# uMatrixPCB_r1_0.net
KiCad netlist of a schematic drawn in EAGLE
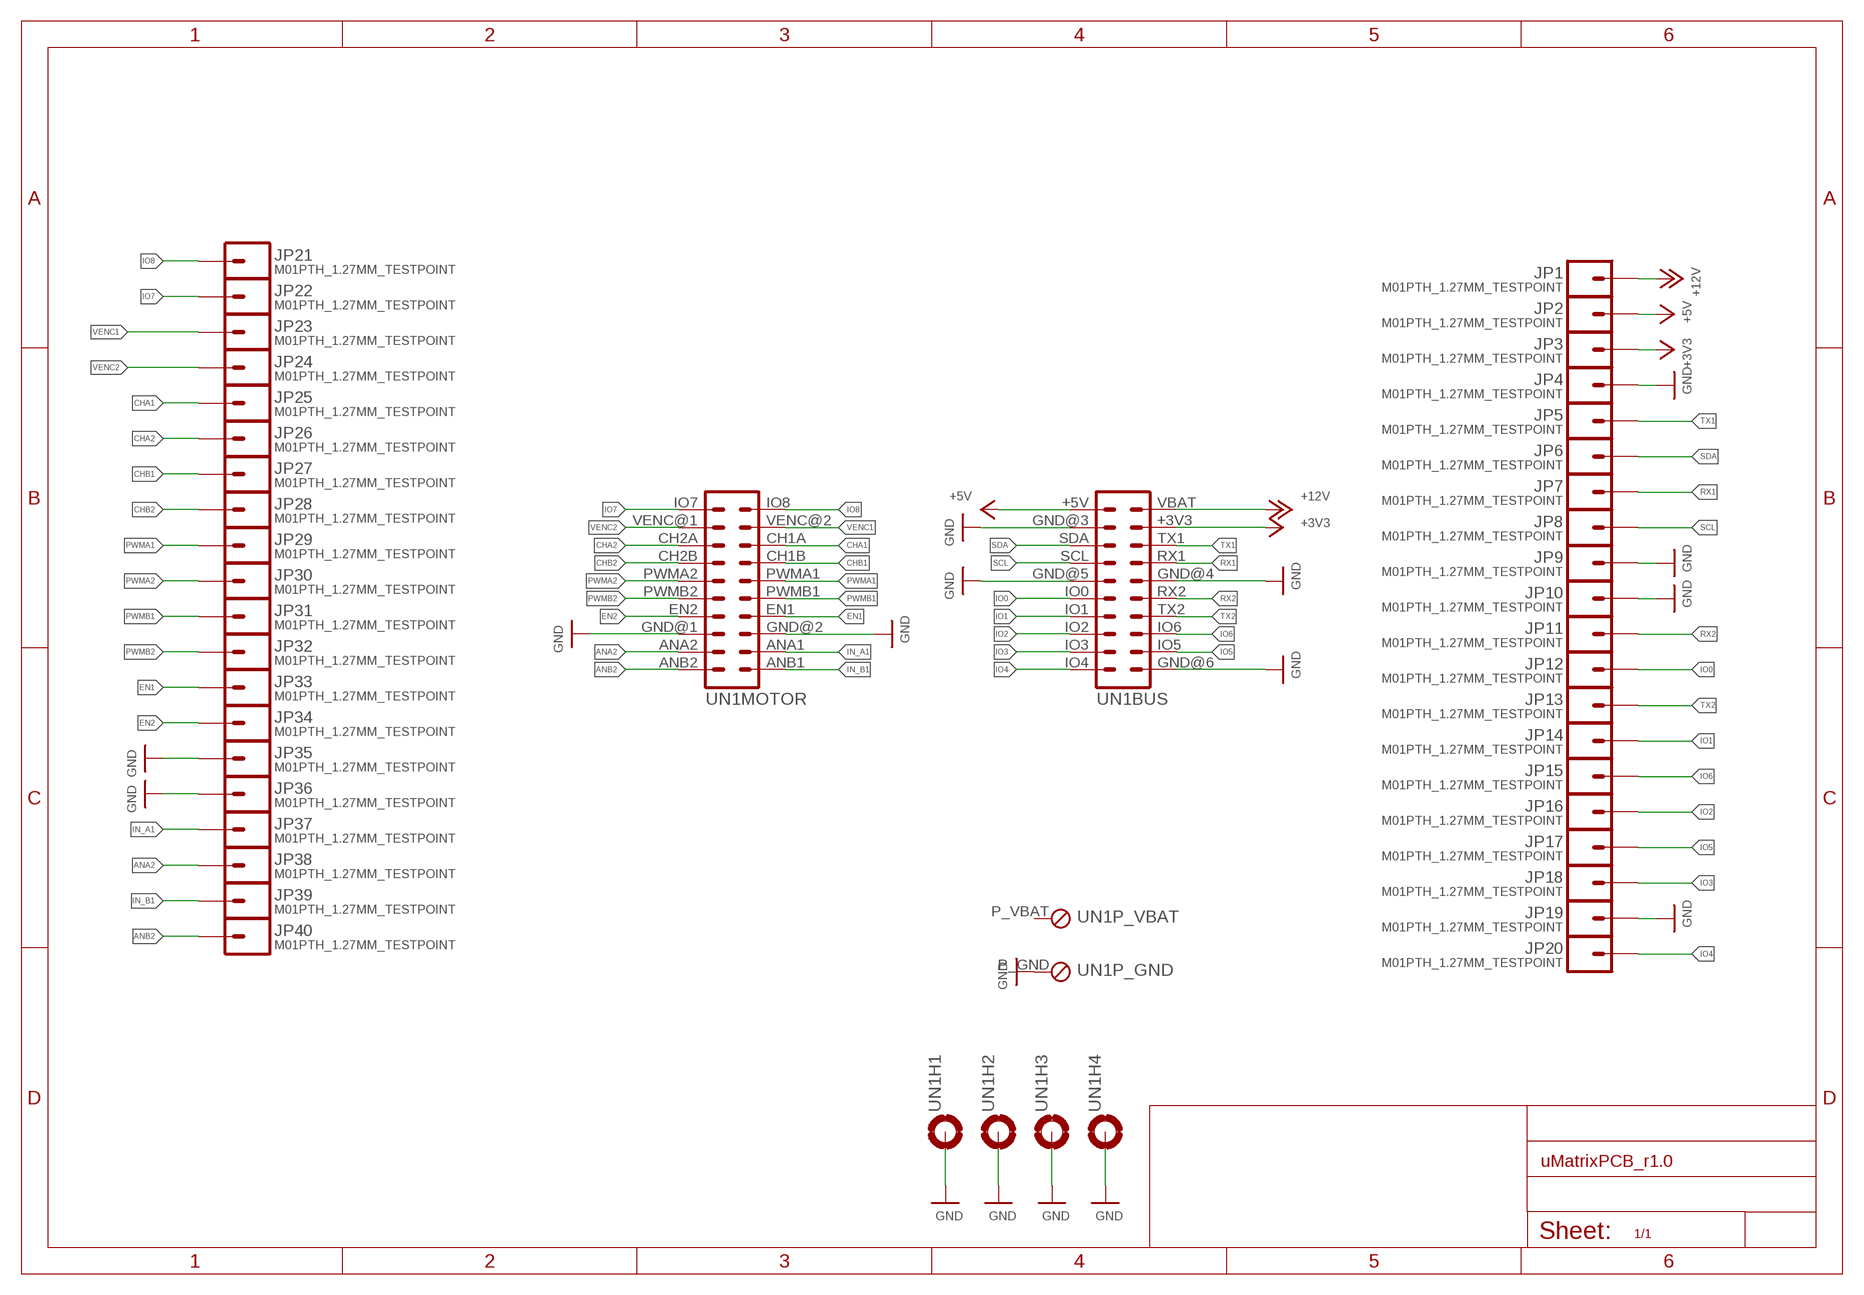
[diagram p0: schematic, sheet 1]

(export (version "E")
  (design (tool "Eeschema 10.0.6"))
  (components
    (comp (ref "JP1")
      (value "M01PTH_1.27MM_TESTPOINT")
      (footprint "eagle-import:1X0.127_TESTPOINT")
      (libsource (lib "eagle-import") (part "M01PTH_1.27MM_TESTPOINT"))
    )
    (comp (ref "JP2")
      (value "M01PTH_1.27MM_TESTPOINT")
      (footprint "eagle-import:1X0.127_TESTPOINT")
      (libsource (lib "eagle-import") (part "M01PTH_1.27MM_TESTPOINT"))
    )
    (comp (ref "JP3")
      (value "M01PTH_1.27MM_TESTPOINT")
      (footprint "eagle-import:1X0.127_TESTPOINT")
      (libsource (lib "eagle-import") (part "M01PTH_1.27MM_TESTPOINT"))
    )
    (comp (ref "JP4")
      (value "M01PTH_1.27MM_TESTPOINT")
      (footprint "eagle-import:1X0.127_TESTPOINT")
      (libsource (lib "eagle-import") (part "M01PTH_1.27MM_TESTPOINT"))
    )
    (comp (ref "JP5")
      (value "M01PTH_1.27MM_TESTPOINT")
      (footprint "eagle-import:1X0.127_TESTPOINT")
      (libsource (lib "eagle-import") (part "M01PTH_1.27MM_TESTPOINT"))
    )
    (comp (ref "JP6")
      (value "M01PTH_1.27MM_TESTPOINT")
      (footprint "eagle-import:1X0.127_TESTPOINT")
      (libsource (lib "eagle-import") (part "M01PTH_1.27MM_TESTPOINT"))
    )
    (comp (ref "JP7")
      (value "M01PTH_1.27MM_TESTPOINT")
      (footprint "eagle-import:1X0.127_TESTPOINT")
      (libsource (lib "eagle-import") (part "M01PTH_1.27MM_TESTPOINT"))
    )
    (comp (ref "JP8")
      (value "M01PTH_1.27MM_TESTPOINT")
      (footprint "eagle-import:1X0.127_TESTPOINT")
      (libsource (lib "eagle-import") (part "M01PTH_1.27MM_TESTPOINT"))
    )
    (comp (ref "JP9")
      (value "M01PTH_1.27MM_TESTPOINT")
      (footprint "eagle-import:1X0.127_TESTPOINT")
      (libsource (lib "eagle-import") (part "M01PTH_1.27MM_TESTPOINT"))
    )
    (comp (ref "JP10")
      (value "M01PTH_1.27MM_TESTPOINT")
      (footprint "eagle-import:1X0.127_TESTPOINT")
      (libsource (lib "eagle-import") (part "M01PTH_1.27MM_TESTPOINT"))
    )
    (comp (ref "JP11")
      (value "M01PTH_1.27MM_TESTPOINT")
      (footprint "eagle-import:1X0.127_TESTPOINT")
      (libsource (lib "eagle-import") (part "M01PTH_1.27MM_TESTPOINT"))
    )
    (comp (ref "JP12")
      (value "M01PTH_1.27MM_TESTPOINT")
      (footprint "eagle-import:1X0.127_TESTPOINT")
      (libsource (lib "eagle-import") (part "M01PTH_1.27MM_TESTPOINT"))
    )
    (comp (ref "JP13")
      (value "M01PTH_1.27MM_TESTPOINT")
      (footprint "eagle-import:1X0.127_TESTPOINT")
      (libsource (lib "eagle-import") (part "M01PTH_1.27MM_TESTPOINT"))
    )
    (comp (ref "JP14")
      (value "M01PTH_1.27MM_TESTPOINT")
      (footprint "eagle-import:1X0.127_TESTPOINT")
      (libsource (lib "eagle-import") (part "M01PTH_1.27MM_TESTPOINT"))
    )
    (comp (ref "JP15")
      (value "M01PTH_1.27MM_TESTPOINT")
      (footprint "eagle-import:1X0.127_TESTPOINT")
      (libsource (lib "eagle-import") (part "M01PTH_1.27MM_TESTPOINT"))
    )
    (comp (ref "JP16")
      (value "M01PTH_1.27MM_TESTPOINT")
      (footprint "eagle-import:1X0.127_TESTPOINT")
      (libsource (lib "eagle-import") (part "M01PTH_1.27MM_TESTPOINT"))
    )
    (comp (ref "JP17")
      (value "M01PTH_1.27MM_TESTPOINT")
      (footprint "eagle-import:1X0.127_TESTPOINT")
      (libsource (lib "eagle-import") (part "M01PTH_1.27MM_TESTPOINT"))
    )
    (comp (ref "JP18")
      (value "M01PTH_1.27MM_TESTPOINT")
      (footprint "eagle-import:1X0.127_TESTPOINT")
      (libsource (lib "eagle-import") (part "M01PTH_1.27MM_TESTPOINT"))
    )
    (comp (ref "JP19")
      (value "M01PTH_1.27MM_TESTPOINT")
      (footprint "eagle-import:1X0.127_TESTPOINT")
      (libsource (lib "eagle-import") (part "M01PTH_1.27MM_TESTPOINT"))
    )
    (comp (ref "JP20")
      (value "M01PTH_1.27MM_TESTPOINT")
      (footprint "eagle-import:1X0.127_TESTPOINT")
      (libsource (lib "eagle-import") (part "M01PTH_1.27MM_TESTPOINT"))
    )
    (comp (ref "JP21")
      (value "M01PTH_1.27MM_TESTPOINT")
      (footprint "eagle-import:1X0.127_TESTPOINT")
      (libsource (lib "eagle-import") (part "M01PTH_1.27MM_TESTPOINT"))
    )
    (comp (ref "JP22")
      (value "M01PTH_1.27MM_TESTPOINT")
      (footprint "eagle-import:1X0.127_TESTPOINT")
      (libsource (lib "eagle-import") (part "M01PTH_1.27MM_TESTPOINT"))
    )
    (comp (ref "JP23")
      (value "M01PTH_1.27MM_TESTPOINT")
      (footprint "eagle-import:1X0.127_TESTPOINT")
      (libsource (lib "eagle-import") (part "M01PTH_1.27MM_TESTPOINT"))
    )
    (comp (ref "JP24")
      (value "M01PTH_1.27MM_TESTPOINT")
      (footprint "eagle-import:1X0.127_TESTPOINT")
      (libsource (lib "eagle-import") (part "M01PTH_1.27MM_TESTPOINT"))
    )
    (comp (ref "JP25")
      (value "M01PTH_1.27MM_TESTPOINT")
      (footprint "eagle-import:1X0.127_TESTPOINT")
      (libsource (lib "eagle-import") (part "M01PTH_1.27MM_TESTPOINT"))
    )
    (comp (ref "JP26")
      (value "M01PTH_1.27MM_TESTPOINT")
      (footprint "eagle-import:1X0.127_TESTPOINT")
      (libsource (lib "eagle-import") (part "M01PTH_1.27MM_TESTPOINT"))
    )
    (comp (ref "JP27")
      (value "M01PTH_1.27MM_TESTPOINT")
      (footprint "eagle-import:1X0.127_TESTPOINT")
      (libsource (lib "eagle-import") (part "M01PTH_1.27MM_TESTPOINT"))
    )
    (comp (ref "JP28")
      (value "M01PTH_1.27MM_TESTPOINT")
      (footprint "eagle-import:1X0.127_TESTPOINT")
      (libsource (lib "eagle-import") (part "M01PTH_1.27MM_TESTPOINT"))
    )
    (comp (ref "JP29")
      (value "M01PTH_1.27MM_TESTPOINT")
      (footprint "eagle-import:1X0.127_TESTPOINT")
      (libsource (lib "eagle-import") (part "M01PTH_1.27MM_TESTPOINT"))
    )
    (comp (ref "JP30")
      (value "M01PTH_1.27MM_TESTPOINT")
      (footprint "eagle-import:1X0.127_TESTPOINT")
      (libsource (lib "eagle-import") (part "M01PTH_1.27MM_TESTPOINT"))
    )
    (comp (ref "JP31")
      (value "M01PTH_1.27MM_TESTPOINT")
      (footprint "eagle-import:1X0.127_TESTPOINT")
      (libsource (lib "eagle-import") (part "M01PTH_1.27MM_TESTPOINT"))
    )
    (comp (ref "JP32")
      (value "M01PTH_1.27MM_TESTPOINT")
      (footprint "eagle-import:1X0.127_TESTPOINT")
      (libsource (lib "eagle-import") (part "M01PTH_1.27MM_TESTPOINT"))
    )
    (comp (ref "JP33")
      (value "M01PTH_1.27MM_TESTPOINT")
      (footprint "eagle-import:1X0.127_TESTPOINT")
      (libsource (lib "eagle-import") (part "M01PTH_1.27MM_TESTPOINT"))
    )
    (comp (ref "JP34")
      (value "M01PTH_1.27MM_TESTPOINT")
      (footprint "eagle-import:1X0.127_TESTPOINT")
      (libsource (lib "eagle-import") (part "M01PTH_1.27MM_TESTPOINT"))
    )
    (comp (ref "JP35")
      (value "M01PTH_1.27MM_TESTPOINT")
      (footprint "eagle-import:1X0.127_TESTPOINT")
      (libsource (lib "eagle-import") (part "M01PTH_1.27MM_TESTPOINT"))
    )
    (comp (ref "JP36")
      (value "M01PTH_1.27MM_TESTPOINT")
      (footprint "eagle-import:1X0.127_TESTPOINT")
      (libsource (lib "eagle-import") (part "M01PTH_1.27MM_TESTPOINT"))
    )
    (comp (ref "JP37")
      (value "M01PTH_1.27MM_TESTPOINT")
      (footprint "eagle-import:1X0.127_TESTPOINT")
      (libsource (lib "eagle-import") (part "M01PTH_1.27MM_TESTPOINT"))
    )
    (comp (ref "JP38")
      (value "M01PTH_1.27MM_TESTPOINT")
      (footprint "eagle-import:1X0.127_TESTPOINT")
      (libsource (lib "eagle-import") (part "M01PTH_1.27MM_TESTPOINT"))
    )
    (comp (ref "JP39")
      (value "M01PTH_1.27MM_TESTPOINT")
      (footprint "eagle-import:1X0.127_TESTPOINT")
      (libsource (lib "eagle-import") (part "M01PTH_1.27MM_TESTPOINT"))
    )
    (comp (ref "JP40")
      (value "M01PTH_1.27MM_TESTPOINT")
      (footprint "eagle-import:1X0.127_TESTPOINT")
      (libsource (lib "eagle-import") (part "M01PTH_1.27MM_TESTPOINT"))
    )
    (comp (ref "UN1")
      (value "UNAV")
      (footprint "eagle-import:UNAV_BOARD")
      (libsource (lib "eagle-import") (part "UNAV"))
    )
  )
  (nets
    (net (code "1") (name "+3V3") (class "Default")
      (node (ref "JP3") (pin "1") (pinfunction "1_1") (pintype "passive"))
      (node (ref "UN1") (pin "+3V3") (pinfunction "3_+3V3") (pintype "passive"))
    )
    (net (code "2") (name "+5V") (class "Default")
      (node (ref "JP2") (pin "1") (pinfunction "1_1") (pintype "passive"))
      (node (ref "UN1") (pin "+5V") (pinfunction "2_+5V") (pintype "passive"))
    )
    (net (code "3") (name "+12V") (class "Default")
      (node (ref "JP1") (pin "1") (pinfunction "1_1") (pintype "passive"))
      (node (ref "UN1") (pin "VBAT") (pinfunction "1_VBAT") (pintype "passive"))
    )
    (net (code "4") (name "ANA2") (class "Default")
      (node (ref "JP38") (pin "1") (pinfunction "1_1") (pintype "passive"))
      (node (ref "UN1") (pin "ANA2") (pinfunction "18_ANA2") (pintype "passive"))
    )
    (net (code "5") (name "ANB2") (class "Default")
      (node (ref "JP40") (pin "1") (pinfunction "1_1") (pintype "passive"))
      (node (ref "UN1") (pin "ANB2") (pinfunction "20_ANB2") (pintype "passive"))
    )
    (net (code "6") (name "CHA1") (class "Default")
      (node (ref "JP25") (pin "1") (pinfunction "1_1") (pintype "passive"))
      (node (ref "UN1") (pin "CH1A") (pinfunction "5_CH1A") (pintype "passive"))
    )
    (net (code "7") (name "CHA2") (class "Default")
      (node (ref "JP26") (pin "1") (pinfunction "1_1") (pintype "passive"))
      (node (ref "UN1") (pin "CH2A") (pinfunction "6_CH2A") (pintype "passive"))
    )
    (net (code "8") (name "CHB1") (class "Default")
      (node (ref "JP27") (pin "1") (pinfunction "1_1") (pintype "passive"))
      (node (ref "UN1") (pin "CH1B") (pinfunction "7_CH1B") (pintype "passive"))
    )
    (net (code "9") (name "CHB2") (class "Default")
      (node (ref "JP28") (pin "1") (pinfunction "1_1") (pintype "passive"))
      (node (ref "UN1") (pin "CH2B") (pinfunction "8_CH2B") (pintype "passive"))
    )
    (net (code "10") (name "EN1") (class "Default")
      (node (ref "JP33") (pin "1") (pinfunction "1_1") (pintype "passive"))
      (node (ref "UN1") (pin "EN1") (pinfunction "13_EN1") (pintype "passive"))
    )
    (net (code "11") (name "EN2") (class "Default")
      (node (ref "JP34") (pin "1") (pinfunction "1_1") (pintype "passive"))
      (node (ref "UN1") (pin "EN2") (pinfunction "14_EN2") (pintype "passive"))
    )
    (net (code "12") (name "GND") (class "Default")
      (node (ref "JP10") (pin "1") (pinfunction "1_1") (pintype "passive"))
      (node (ref "JP19") (pin "1") (pinfunction "1_1") (pintype "passive"))
      (node (ref "JP35") (pin "1") (pinfunction "1_1") (pintype "passive"))
      (node (ref "JP36") (pin "1") (pinfunction "1_1") (pintype "passive"))
      (node (ref "JP4") (pin "1") (pinfunction "1_1") (pintype "passive"))
      (node (ref "JP9") (pin "1") (pinfunction "1_1") (pintype "passive"))
      (node (ref "UN1") (pin "GND@1") (pinfunction "16_GND@1") (pintype "passive"))
      (node (ref "UN1") (pin "GND@2") (pinfunction "15_GND@2") (pintype "passive"))
      (node (ref "UN1") (pin "GND@3") (pinfunction "4_GND@3") (pintype "passive"))
      (node (ref "UN1") (pin "GND@4") (pinfunction "9_GND@4") (pintype "passive"))
      (node (ref "UN1") (pin "GND@5") (pinfunction "10_GND@5") (pintype "passive"))
      (node (ref "UN1") (pin "GND@6") (pinfunction "19_GND@6") (pintype "passive"))
      (node (ref "UN1") (pin "H1") (pinfunction "MOUNT_H1") (pintype "passive"))
      (node (ref "UN1") (pin "H2") (pinfunction "MOUNT_H2") (pintype "passive"))
      (node (ref "UN1") (pin "H3") (pinfunction "MOUNT_H3") (pintype "passive"))
      (node (ref "UN1") (pin "H4") (pinfunction "MOUNT_H4") (pintype "passive"))
      (node (ref "UN1") (pin "P_GND") (pinfunction "1_P_GND") (pintype "passive"))
    )
    (net (code "13") (name "IN_A1") (class "Default")
      (node (ref "JP37") (pin "1") (pinfunction "1_1") (pintype "passive"))
      (node (ref "UN1") (pin "ANA1") (pinfunction "17_ANA1") (pintype "passive"))
    )
    (net (code "14") (name "IN_B1") (class "Default")
      (node (ref "JP39") (pin "1") (pinfunction "1_1") (pintype "passive"))
      (node (ref "UN1") (pin "ANB1") (pinfunction "19_ANB1") (pintype "passive"))
    )
    (net (code "15") (name "IO0") (class "Default")
      (node (ref "JP12") (pin "1") (pinfunction "1_1") (pintype "passive"))
      (node (ref "UN1") (pin "IO0") (pinfunction "12_IO0") (pintype "passive"))
    )
    (net (code "16") (name "IO1") (class "Default")
      (node (ref "JP14") (pin "1") (pinfunction "1_1") (pintype "passive"))
      (node (ref "UN1") (pin "IO1") (pinfunction "14_IO1") (pintype "passive"))
    )
    (net (code "17") (name "IO2") (class "Default")
      (node (ref "JP16") (pin "1") (pinfunction "1_1") (pintype "passive"))
      (node (ref "UN1") (pin "IO2") (pinfunction "16_IO2") (pintype "passive"))
    )
    (net (code "18") (name "IO3") (class "Default")
      (node (ref "JP18") (pin "1") (pinfunction "1_1") (pintype "passive"))
      (node (ref "UN1") (pin "IO3") (pinfunction "18_IO3") (pintype "passive"))
    )
    (net (code "19") (name "IO4") (class "Default")
      (node (ref "JP20") (pin "1") (pinfunction "1_1") (pintype "passive"))
      (node (ref "UN1") (pin "IO4") (pinfunction "20_IO4") (pintype "passive"))
    )
    (net (code "20") (name "IO5") (class "Default")
      (node (ref "JP17") (pin "1") (pinfunction "1_1") (pintype "passive"))
      (node (ref "UN1") (pin "IO5") (pinfunction "17_IO5") (pintype "passive"))
    )
    (net (code "21") (name "IO6") (class "Default")
      (node (ref "JP15") (pin "1") (pinfunction "1_1") (pintype "passive"))
      (node (ref "UN1") (pin "IO6") (pinfunction "15_IO6") (pintype "passive"))
    )
    (net (code "22") (name "IO7") (class "Default")
      (node (ref "JP22") (pin "1") (pinfunction "1_1") (pintype "passive"))
      (node (ref "UN1") (pin "IO7") (pinfunction "2_IO7") (pintype "passive"))
    )
    (net (code "23") (name "IO8") (class "Default")
      (node (ref "JP21") (pin "1") (pinfunction "1_1") (pintype "passive"))
      (node (ref "UN1") (pin "IO8") (pinfunction "1_IO8") (pintype "passive"))
    )
    (net (code "24") (name "PWMA1") (class "Default")
      (node (ref "JP29") (pin "1") (pinfunction "1_1") (pintype "passive"))
      (node (ref "UN1") (pin "PWMA1") (pinfunction "9_PWMA1") (pintype "passive"))
    )
    (net (code "25") (name "PWMA2") (class "Default")
      (node (ref "JP30") (pin "1") (pinfunction "1_1") (pintype "passive"))
      (node (ref "UN1") (pin "PWMA2") (pinfunction "10_PWMA2") (pintype "passive"))
    )
    (net (code "26") (name "PWMB1") (class "Default")
      (node (ref "JP31") (pin "1") (pinfunction "1_1") (pintype "passive"))
      (node (ref "UN1") (pin "PWMB1") (pinfunction "11_PWMB1") (pintype "passive"))
    )
    (net (code "27") (name "PWMB2") (class "Default")
      (node (ref "JP32") (pin "1") (pinfunction "1_1") (pintype "passive"))
      (node (ref "UN1") (pin "PWMB2") (pinfunction "12_PWMB2") (pintype "passive"))
    )
    (net (code "28") (name "RX1") (class "Default")
      (node (ref "JP7") (pin "1") (pinfunction "1_1") (pintype "passive"))
      (node (ref "UN1") (pin "RX1") (pinfunction "7_RX1") (pintype "passive"))
    )
    (net (code "29") (name "RX2") (class "Default")
      (node (ref "JP11") (pin "1") (pinfunction "1_1") (pintype "passive"))
      (node (ref "UN1") (pin "RX2") (pinfunction "11_RX2") (pintype "passive"))
    )
    (net (code "30") (name "SCL") (class "Default")
      (node (ref "JP8") (pin "1") (pinfunction "1_1") (pintype "passive"))
      (node (ref "UN1") (pin "SCL") (pinfunction "8_SCL") (pintype "passive"))
    )
    (net (code "31") (name "SDA") (class "Default")
      (node (ref "JP6") (pin "1") (pinfunction "1_1") (pintype "passive"))
      (node (ref "UN1") (pin "SDA") (pinfunction "6_SDA") (pintype "passive"))
    )
    (net (code "32") (name "TX1") (class "Default")
      (node (ref "JP5") (pin "1") (pinfunction "1_1") (pintype "passive"))
      (node (ref "UN1") (pin "TX1") (pinfunction "5_TX1") (pintype "passive"))
    )
    (net (code "33") (name "TX2") (class "Default")
      (node (ref "JP13") (pin "1") (pinfunction "1_1") (pintype "passive"))
      (node (ref "UN1") (pin "TX2") (pinfunction "13_TX2") (pintype "passive"))
    )
    (net (code "34") (name "VENC1") (class "Default")
      (node (ref "JP23") (pin "1") (pinfunction "1_1") (pintype "passive"))
      (node (ref "UN1") (pin "VENC@2") (pinfunction "3_VENC@2") (pintype "passive"))
    )
    (net (code "35") (name "VENC2") (class "Default")
      (node (ref "JP24") (pin "1") (pinfunction "1_1") (pintype "passive"))
      (node (ref "UN1") (pin "VENC@1") (pinfunction "4_VENC@1") (pintype "passive"))
    )
    (net (code "36") (name "unconnected-(UN1H-1-PadP_VBAT)") (class "Default")
      (node (ref "UN1") (pin "P_VBAT") (pinfunction "1_P_VBAT") (pintype "passive"))
    )
  )
)
